# XM125_Breakout.net
KiCad netlist of a schematic drawn in EAGLE
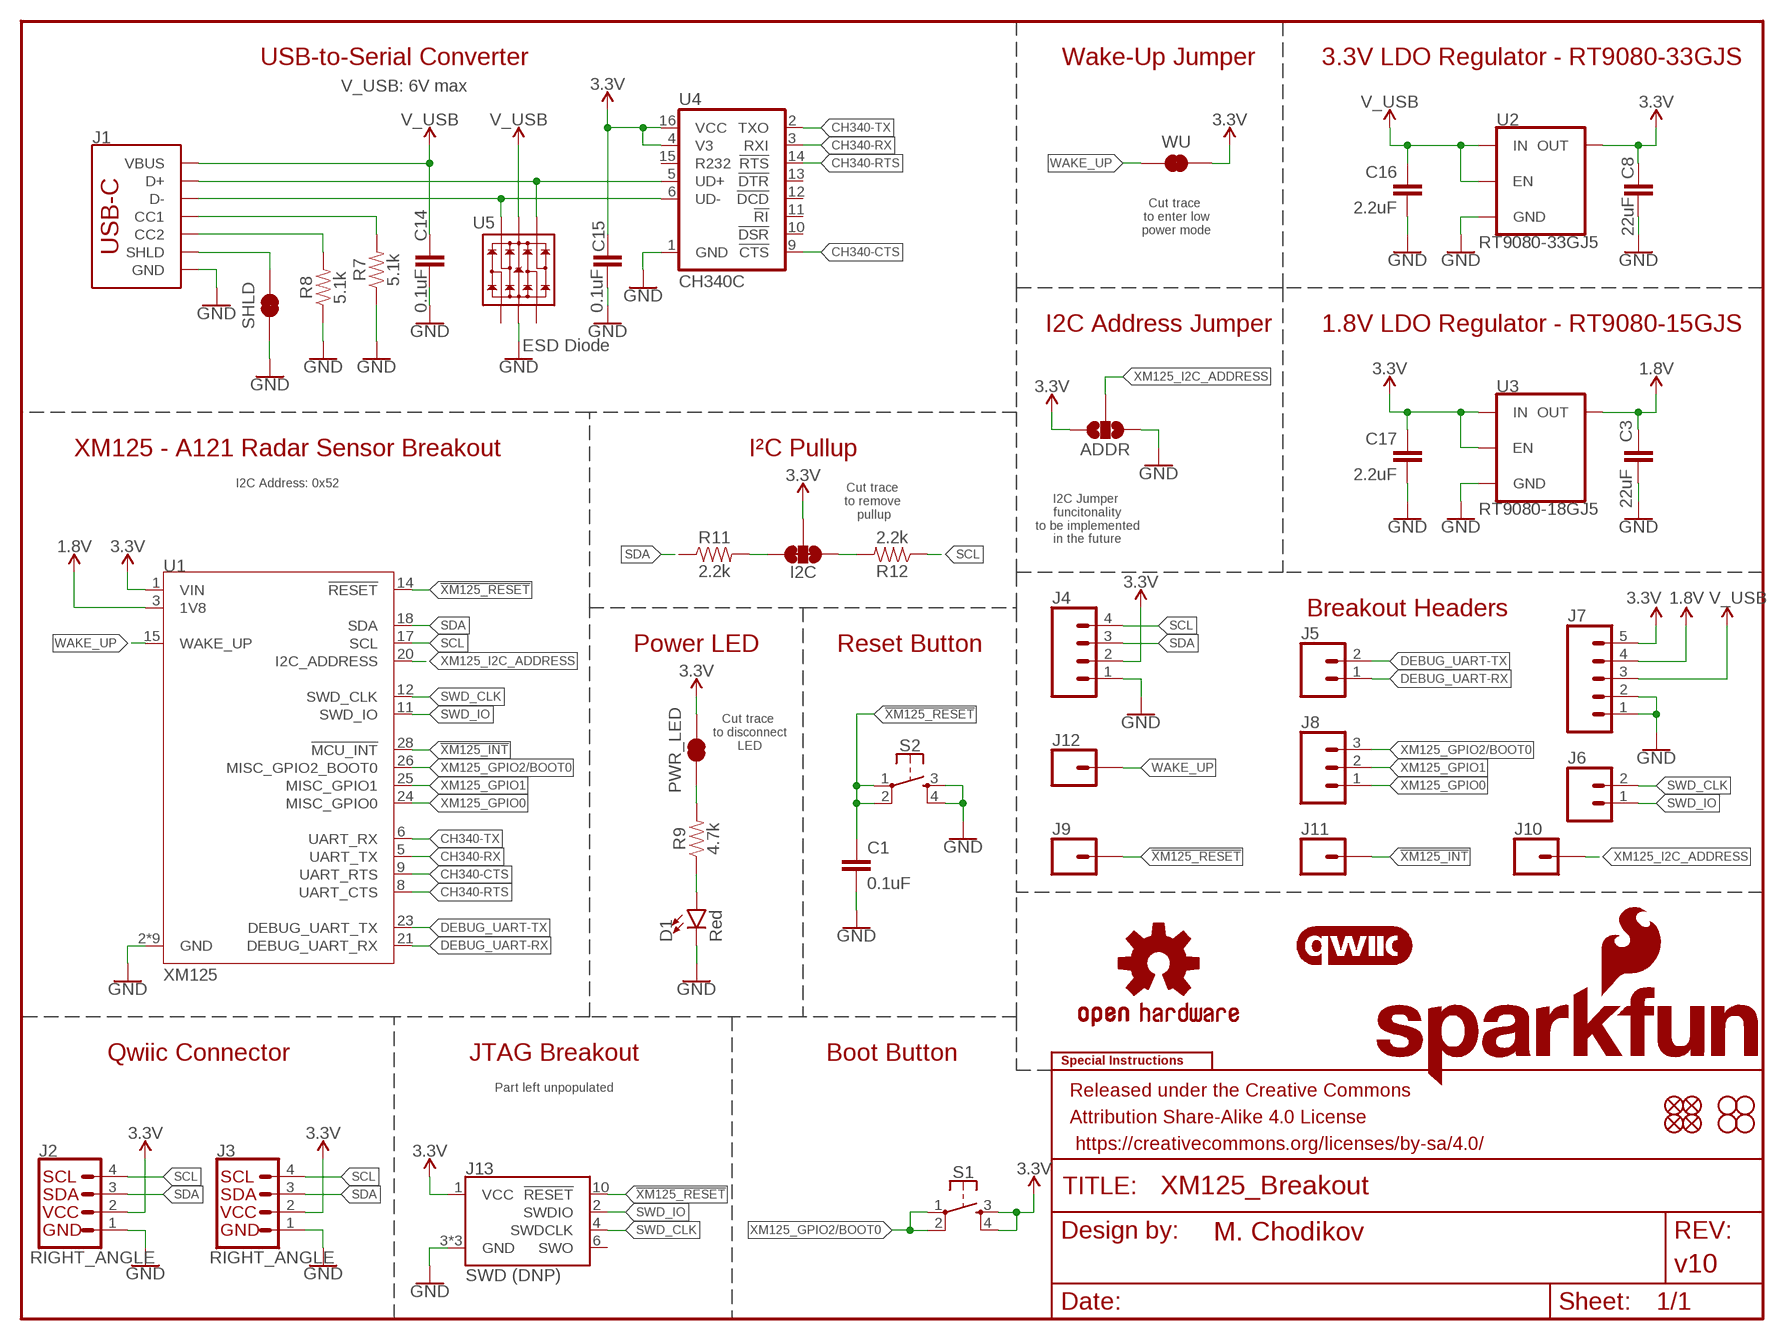
[diagram p0: schematic, sheet 1]

(export (version "E")
  (design (tool "Eeschema 10.0.6"))
  (components
    (comp (ref "ADDR")
      (value "JUMPER-SMT_3_NO_SILK")
      (footprint "eagle-import:SMT-JUMPER_3_NO_SILK")
      (libsource (lib "eagle-import") (part "JUMPER-SMT_3_NO_SILK"))
    )
    (comp (ref "C1")
      (value "0.1uF")
      (footprint "eagle-import:0603")
      (libsource (lib "eagle-import") (part "0.1UF-0603-25V-(+80/-20%)"))
    )
    (comp (ref "C3")
      (value "22uF")
      (footprint "eagle-import:0603")
      (libsource (lib "eagle-import") (part "22UF-0603-6.3V-20%"))
    )
    (comp (ref "C8")
      (value "22uF")
      (footprint "eagle-import:0603")
      (libsource (lib "eagle-import") (part "22UF-0603-6.3V-20%"))
    )
    (comp (ref "C14")
      (value "0.1uF")
      (footprint "eagle-import:0603")
      (libsource (lib "eagle-import") (part "0.1UF-0603-25V-(+80/-20%)"))
    )
    (comp (ref "C15")
      (value "0.1uF")
      (footprint "eagle-import:0603")
      (libsource (lib "eagle-import") (part "0.1UF-0603-25V-(+80/-20%)"))
    )
    (comp (ref "C16")
      (value "2.2uF")
      (footprint "eagle-import:0603")
      (libsource (lib "eagle-import") (part "2.2UF-0603-10V-20%"))
    )
    (comp (ref "C17")
      (value "2.2uF")
      (footprint "eagle-import:0603")
      (libsource (lib "eagle-import") (part "2.2UF-0603-10V-20%"))
    )
    (comp (ref "D1")
      (value "Red")
      (footprint "eagle-import:LED-0603")
      (libsource (lib "eagle-import") (part "LED-RED_0603-KB"))
    )
    (comp (ref "FD1")
      (value "FIDUCIAL1X2")
      (footprint "eagle-import:FIDUCIAL-1X2")
      (libsource (lib "eagle-import") (part "FIDUCIAL1X2"))
    )
    (comp (ref "FD2")
      (value "FIDUCIAL1X2")
      (footprint "eagle-import:FIDUCIAL-1X2")
      (libsource (lib "eagle-import") (part "FIDUCIAL1X2"))
    )
    (comp (ref "FD3")
      (value "FIDUCIAL1X2")
      (footprint "eagle-import:FIDUCIAL-1X2")
      (libsource (lib "eagle-import") (part "FIDUCIAL1X2"))
    )
    (comp (ref "FD4")
      (value "FIDUCIAL1X2")
      (footprint "eagle-import:FIDUCIAL-1X2")
      (libsource (lib "eagle-import") (part "FIDUCIAL1X2"))
    )
    (comp (ref "FRAME2")
      (value "FRAME-LETTER")
      (footprint "eagle-import:CREATIVE_COMMONS")
      (fields (field (name "DESIGNER") "M. Chodikov") (field (name "REV") "v10"))
      (libsource (lib "eagle-import") (part "FRAME-LETTER"))
    )
    (comp (ref "H1")
      (value "STAND-OFF")
      (footprint "eagle-import:STAND-OFF")
      (libsource (lib "eagle-import") (part "STAND-OFF"))
    )
    (comp (ref "H2")
      (value "STAND-OFF")
      (footprint "eagle-import:STAND-OFF")
      (libsource (lib "eagle-import") (part "STAND-OFF"))
    )
    (comp (ref "H3")
      (value "STAND-OFF")
      (footprint "eagle-import:STAND-OFF")
      (libsource (lib "eagle-import") (part "STAND-OFF"))
    )
    (comp (ref "H4")
      (value "STAND-OFF")
      (footprint "eagle-import:STAND-OFF")
      (libsource (lib "eagle-import") (part "STAND-OFF"))
    )
    (comp (ref "I2C")
      (value "JUMPER-SMT_3_2-NC_TRACE_SILK")
      (footprint "eagle-import:SMT-JUMPER_3_2-NC_TRACE_SILK")
      (libsource (lib "eagle-import") (part "JUMPER-SMT_3_2-NC_TRACE_SILK"))
    )
    (comp (ref "J1")
      (value "USB_C_2-LAYER_PADS")
      (footprint "eagle-import:USB-C-16P-2LAYER-PADS")
      (libsource (lib "eagle-import") (part "USB_C_2-LAYER_PADS"))
    )
    (comp (ref "J2")
      (value "RIGHT_ANGLE")
      (footprint "eagle-import:JST04_1MM_RA")
      (libsource (lib "eagle-import") (part "QWIIC_CONNECTORJS-1MM"))
    )
    (comp (ref "J3")
      (value "RIGHT_ANGLE")
      (footprint "eagle-import:JST04_1MM_RA")
      (libsource (lib "eagle-import") (part "QWIIC_CONNECTORJS-1MM"))
    )
    (comp (ref "J4")
      (value "CONN_041X04_NO_SILK")
      (footprint "eagle-import:1X04_NO_SILK")
      (libsource (lib "eagle-import") (part "CONN_041X04_NO_SILK"))
    )
    (comp (ref "J5")
      (value "CONN_021X02_NO_SILK")
      (footprint "eagle-import:1X02_NO_SILK")
      (libsource (lib "eagle-import") (part "CONN_021X02_NO_SILK"))
    )
    (comp (ref "J6")
      (value "CONN_021X02_NO_SILK")
      (footprint "eagle-import:1X02_NO_SILK")
      (libsource (lib "eagle-import") (part "CONN_021X02_NO_SILK"))
    )
    (comp (ref "J7")
      (value "CONN_05NO_SILK")
      (footprint "eagle-import:1X05_NO_SILK")
      (libsource (lib "eagle-import") (part "CONN_05NO_SILK"))
    )
    (comp (ref "J8")
      (value "CONN_031X03_NO_SILK")
      (footprint "eagle-import:1X03_NO_SILK")
      (libsource (lib "eagle-import") (part "CONN_031X03_NO_SILK"))
    )
    (comp (ref "J9")
      (value "CONN_01PTH_NO_SILK_STAND")
      (footprint "eagle-import:1X01_NO_SILK_STAND")
      (libsource (lib "eagle-import") (part "CONN_01PTH_NO_SILK_STAND"))
    )
    (comp (ref "J10")
      (value "CONN_01PTH_NO_SILK_STAND")
      (footprint "eagle-import:1X01_NO_SILK_STAND")
      (libsource (lib "eagle-import") (part "CONN_01PTH_NO_SILK_STAND"))
    )
    (comp (ref "J11")
      (value "CONN_01PTH_NO_SILK_STAND")
      (footprint "eagle-import:1X01_NO_SILK_STAND")
      (libsource (lib "eagle-import") (part "CONN_01PTH_NO_SILK_STAND"))
    )
    (comp (ref "J12")
      (value "CONN_01PTH_NO_SILK_STAND")
      (footprint "eagle-import:1X01_NO_SILK_STAND")
      (libsource (lib "eagle-import") (part "CONN_01PTH_NO_SILK_STAND"))
    )
    (comp (ref "J13")
      (value "SWD (DNP)")
      (footprint "eagle-import:2X5-SMD-UNSHROUDED_DNP_NO_PASTE")
      (libsource (lib "eagle-import") (part "CORTEX_JTAG_DEBUG_MINIMUM_SMD_UNSHROUDED_DNP_NO_PASTE"))
    )
    (comp (ref "LOGO1")
      (value "SPECIAL_INSTRUCTIONS-ORDERING")
      (footprint "eagle-import:ORDERING_INSTRUCTIONS")
      (libsource (lib "eagle-import") (part "SPECIAL_INSTRUCTIONS-ORDERING"))
    )
    (comp (ref "LOGO2")
      (value "QWIIC_LOGO_4MM")
      (footprint "eagle-import:QWIIC_4MM")
      (libsource (lib "eagle-import") (part "QWIIC_LOGO_4MM"))
    )
    (comp (ref "LOGO3")
      (value "SFE_LOGO_NAME_FLAME.1_INCH")
      (footprint "eagle-import:SFE_LOGO_NAME_FLAME_.1")
      (libsource (lib "eagle-import") (part "SFE_LOGO_NAME_FLAME.1_INCH"))
    )
    (comp (ref "LOGO4")
      (value "OSHW-LOGOS")
      (footprint "eagle-import:OSHW-LOGO-S")
      (libsource (lib "eagle-import") (part "OSHW-LOGOS"))
    )
    (comp (ref "LOGO5")
      (value "SFE_LOGO_FLAME.1_INCH")
      (footprint "eagle-import:SFE_LOGO_FLAME_.1")
      (libsource (lib "eagle-import") (part "SFE_LOGO_FLAME.1_INCH"))
    )
    (comp (ref "LOGO6")
      (value "SFE_LOGO_NAME_FLAME.1_INCH")
      (footprint "eagle-import:SFE_LOGO_NAME_FLAME_.1")
      (libsource (lib "eagle-import") (part "SFE_LOGO_NAME_FLAME.1_INCH"))
    )
    (comp (ref "PWR_LED")
      (value "JUMPER-SMT_2_NC_TRACE_SILK")
      (footprint "eagle-import:SMT-JUMPER_2_NC_TRACE_SILK")
      (libsource (lib "eagle-import") (part "JUMPER-SMT_2_NC_TRACE_SILK"))
    )
    (comp (ref "R7")
      (value "5.1k")
      (footprint "eagle-import:0603")
      (libsource (lib "eagle-import") (part "5.1KOHM5.1KOHM-0603-1/10W-1%"))
    )
    (comp (ref "R8")
      (value "5.1k")
      (footprint "eagle-import:0603")
      (libsource (lib "eagle-import") (part "5.1KOHM5.1KOHM-0603-1/10W-1%"))
    )
    (comp (ref "R9")
      (value "4.7k")
      (footprint "eagle-import:0603")
      (libsource (lib "eagle-import") (part "4.7KOHM-0603-1/10W-1%"))
    )
    (comp (ref "R11")
      (value "2.2k")
      (footprint "eagle-import:0603")
      (libsource (lib "eagle-import") (part "2.2KOHM-0603-1/10W-1%"))
    )
    (comp (ref "R12")
      (value "2.2k")
      (footprint "eagle-import:0603")
      (libsource (lib "eagle-import") (part "2.2KOHM-0603-1/10W-1%"))
    )
    (comp (ref "S1")
      (value "MOMENTARY-SWITCH-SPST-2-SMD-5.2MM")
      (footprint "eagle-import:TACTILE_SWITCH_SMD_5.2MM")
      (libsource (lib "eagle-import") (part "MOMENTARY-SWITCH-SPST-2-SMD-5.2MM"))
    )
    (comp (ref "S2")
      (value "MOMENTARY-SWITCH-SPST-2-SMD-5.2MM")
      (footprint "eagle-import:TACTILE_SWITCH_SMD_5.2MM")
      (libsource (lib "eagle-import") (part "MOMENTARY-SWITCH-SPST-2-SMD-5.2MM"))
    )
    (comp (ref "SHLD")
      (value "JUMPER-SMT_2_NC_TRACE_SILK")
      (footprint "eagle-import:SMT-JUMPER_2_NC_TRACE_SILK")
      (libsource (lib "eagle-import") (part "JUMPER-SMT_2_NC_TRACE_SILK"))
    )
    (comp (ref "U1")
      (value "XM125")
      (footprint "eagle-import:XM125_ACC")
      (libsource (lib "eagle-import") (part "XM125"))
    )
    (comp (ref "U2")
      (value "RT9080-33GJ5")
      (footprint "eagle-import:SOT23-5")
      (libsource (lib "eagle-import") (part "V_REG_RT9080"))
    )
    (comp (ref "U3")
      (value "RT9080-18GJ5")
      (footprint "eagle-import:SOT23-5")
      (libsource (lib "eagle-import") (part "RT9080-18GJ5"))
    )
    (comp (ref "U4")
      (value "CH340C")
      (footprint "eagle-import:SO016")
      (libsource (lib "eagle-import") (part "CH340C"))
    )
    (comp (ref "U5")
      (value "ESD Diode")
      (footprint "eagle-import:SOT-23-6")
      (libsource (lib "eagle-import") (part "TVS_DIODE_ARRAY_DT1042-04SO-7"))
    )
    (comp (ref "WU")
      (value "JUMPER-SMT_2_NC_TRACE_SILK")
      (footprint "eagle-import:SMT-JUMPER_2_NC_TRACE_SILK")
      (libsource (lib "eagle-import") (part "JUMPER-SMT_2_NC_TRACE_SILK"))
    )
  )
  (nets
    (net (code "1") (name "/~{XM125_INT}") (class "Default")
      (node (ref "J11") (pin "1") (pinfunction "1_1") (pintype "passive"))
      (node (ref "U1") (pin "28") (pinfunction "~{MCU_INT}_28") (pintype "passive"))
    )
    (net (code "2") (name "/~{XM125_RESET}") (class "Default")
      (node (ref "C1") (pin "2") (pinfunction "2_2") (pintype "passive"))
      (node (ref "J13") (pin "10") (pinfunction "~{RESET}_10") (pintype "bidirectional"))
      (node (ref "J9") (pin "1") (pinfunction "1_1") (pintype "passive"))
      (node (ref "S2") (pin "1") (pinfunction "1_1") (pintype "passive"))
      (node (ref "S2") (pin "2") (pinfunction "2_2") (pintype "passive"))
      (node (ref "U1") (pin "14") (pinfunction "~{RESET}_14") (pintype "passive"))
    )
    (net (code "3") (name "1.8V") (class "Default")
      (node (ref "C3") (pin "1") (pinfunction "1_1") (pintype "passive"))
      (node (ref "J7") (pin "4") (pinfunction "4_4") (pintype "passive"))
      (node (ref "U1") (pin "3") (pinfunction "1V8_3") (pintype "power_in"))
      (node (ref "U3") (pin "5") (pinfunction "OUT_5") (pintype "passive"))
    )
    (net (code "4") (name "3.3V") (class "Default")
      (node (ref "ADDR") (pin "3") (pinfunction "3_3") (pintype "passive"))
      (node (ref "C15") (pin "1") (pinfunction "1_1") (pintype "passive"))
      (node (ref "C17") (pin "1") (pinfunction "1_1") (pintype "passive"))
      (node (ref "C8") (pin "1") (pinfunction "1_1") (pintype "passive"))
      (node (ref "I2C") (pin "2") (pinfunction "2_2") (pintype "passive"))
      (node (ref "J13") (pin "1") (pinfunction "VCC_1") (pintype "bidirectional"))
      (node (ref "J2") (pin "2") (pinfunction "2_2") (pintype "power_in"))
      (node (ref "J3") (pin "2") (pinfunction "2_2") (pintype "power_in"))
      (node (ref "J4") (pin "2") (pinfunction "2_2") (pintype "passive"))
      (node (ref "J7") (pin "5") (pinfunction "5_5") (pintype "passive"))
      (node (ref "PWR_LED") (pin "2") (pinfunction "2_2") (pintype "passive"))
      (node (ref "S1") (pin "3") (pinfunction "3_3") (pintype "passive"))
      (node (ref "S1") (pin "4") (pinfunction "4_4") (pintype "passive"))
      (node (ref "U1") (pin "1") (pinfunction "VIN_1") (pintype "power_in"))
      (node (ref "U2") (pin "5") (pinfunction "OUT_5") (pintype "passive"))
      (node (ref "U3") (pin "1") (pinfunction "IN_1") (pintype "input"))
      (node (ref "U3") (pin "3") (pinfunction "EN_3") (pintype "input"))
      (node (ref "U4") (pin "16") (pinfunction "VCC_16") (pintype "bidirectional"))
      (node (ref "U4") (pin "4") (pinfunction "V3_4") (pintype "bidirectional"))
      (node (ref "WU") (pin "2") (pinfunction "2_2") (pintype "passive"))
    )
    (net (code "5") (name "CH340-CTS") (class "Default")
      (node (ref "U1") (pin "9") (pinfunction "UART_RTS_9") (pintype "passive"))
      (node (ref "U4") (pin "9") (pinfunction "~{CTS}_9") (pintype "bidirectional"))
    )
    (net (code "6") (name "CH340-RTS") (class "Default")
      (node (ref "U1") (pin "8") (pinfunction "UART_CTS_8") (pintype "passive"))
      (node (ref "U4") (pin "14") (pinfunction "~{RTS}_14") (pintype "bidirectional"))
    )
    (net (code "7") (name "CH340-RX") (class "Default")
      (node (ref "U1") (pin "5") (pinfunction "UART_TX_5") (pintype "passive"))
      (node (ref "U4") (pin "3") (pinfunction "RXI_3") (pintype "bidirectional"))
    )
    (net (code "8") (name "CH340-TX") (class "Default")
      (node (ref "U1") (pin "6") (pinfunction "UART_RX_6") (pintype "passive"))
      (node (ref "U4") (pin "2") (pinfunction "TXO_2") (pintype "bidirectional"))
    )
    (net (code "9") (name "DEBUG_UART-RX") (class "Default")
      (node (ref "J5") (pin "1") (pinfunction "1_1") (pintype "passive"))
      (node (ref "U1") (pin "21") (pinfunction "DEBUG_UART_RX_21") (pintype "passive"))
    )
    (net (code "10") (name "DEBUG_UART-TX") (class "Default")
      (node (ref "J5") (pin "2") (pinfunction "2_2") (pintype "passive"))
      (node (ref "U1") (pin "23") (pinfunction "DEBUG_UART_TX_23") (pintype "passive"))
    )
    (net (code "11") (name "GND") (class "Default")
      (node (ref "ADDR") (pin "1") (pinfunction "1_1") (pintype "passive"))
      (node (ref "C1") (pin "1") (pinfunction "1_1") (pintype "passive"))
      (node (ref "C14") (pin "2") (pinfunction "2_2") (pintype "passive"))
      (node (ref "C15") (pin "2") (pinfunction "2_2") (pintype "passive"))
      (node (ref "C16") (pin "2") (pinfunction "2_2") (pintype "passive"))
      (node (ref "C17") (pin "2") (pinfunction "2_2") (pintype "passive"))
      (node (ref "C3") (pin "2") (pinfunction "2_2") (pintype "passive"))
      (node (ref "C8") (pin "2") (pinfunction "2_2") (pintype "passive"))
      (node (ref "D1") (pin "C") (pinfunction "C_C") (pintype "passive"))
      (node (ref "J1") (pin "GND") (pinfunction "GND_GND") (pintype "bidirectional"))
      (node (ref "J1") (pin "GND2") (pinfunction "GND_GND2") (pintype "bidirectional"))
      (node (ref "J13") (pin "3") (pinfunction "GND_3") (pintype "bidirectional"))
      (node (ref "J13") (pin "5") (pinfunction "GND_5") (pintype "bidirectional"))
      (node (ref "J13") (pin "9") (pinfunction "GND_9") (pintype "bidirectional"))
      (node (ref "J2") (pin "1") (pinfunction "1_1") (pintype "power_in"))
      (node (ref "J3") (pin "1") (pinfunction "1_1") (pintype "power_in"))
      (node (ref "J4") (pin "1") (pinfunction "1_1") (pintype "passive"))
      (node (ref "J7") (pin "1") (pinfunction "1_1") (pintype "passive"))
      (node (ref "J7") (pin "2") (pinfunction "2_2") (pintype "passive"))
      (node (ref "R7") (pin "1") (pinfunction "1_1") (pintype "passive"))
      (node (ref "R8") (pin "1") (pinfunction "1_1") (pintype "passive"))
      (node (ref "S2") (pin "3") (pinfunction "3_3") (pintype "passive"))
      (node (ref "S2") (pin "4") (pinfunction "4_4") (pintype "passive"))
      (node (ref "SHLD") (pin "1") (pinfunction "1_1") (pintype "passive"))
      (node (ref "U1") (pin "10") (pinfunction "GND_10") (pintype "passive"))
      (node (ref "U1") (pin "13") (pinfunction "GND_13") (pintype "passive"))
      (node (ref "U1") (pin "16") (pinfunction "GND_16") (pintype "passive"))
      (node (ref "U1") (pin "19") (pinfunction "GND_19") (pintype "passive"))
      (node (ref "U1") (pin "2") (pinfunction "GND_2") (pintype "passive"))
      (node (ref "U1") (pin "22") (pinfunction "GND_22") (pintype "passive"))
      (node (ref "U1") (pin "27") (pinfunction "GND_27") (pintype "passive"))
      (node (ref "U1") (pin "4") (pinfunction "GND_4") (pintype "passive"))
      (node (ref "U1") (pin "7") (pinfunction "GND_7") (pintype "passive"))
      (node (ref "U2") (pin "2") (pinfunction "GND_2") (pintype "input"))
      (node (ref "U3") (pin "2") (pinfunction "GND_2") (pintype "input"))
      (node (ref "U4") (pin "1") (pinfunction "GND_1") (pintype "bidirectional"))
      (node (ref "U5") (pin "2") (pinfunction "VSS_2") (pintype "bidirectional"))
    )
    (net (code "12") (name "Net-(D1-PadA)") (class "Default")
      (node (ref "D1") (pin "A") (pinfunction "A_A") (pintype "passive"))
      (node (ref "R9") (pin "1") (pinfunction "1_1") (pintype "passive"))
    )
    (net (code "13") (name "Net-(I2C-Pad1)") (class "Default")
      (node (ref "I2C") (pin "1") (pinfunction "1_1") (pintype "passive"))
      (node (ref "R12") (pin "2") (pinfunction "2_2") (pintype "passive"))
    )
    (net (code "14") (name "Net-(I2C-Pad3)") (class "Default")
      (node (ref "I2C") (pin "3") (pinfunction "3_3") (pintype "passive"))
      (node (ref "R11") (pin "2") (pinfunction "2_2") (pintype "passive"))
    )
    (net (code "15") (name "Net-(J1-CC1)") (class "Default")
      (node (ref "J1") (pin "A5") (pinfunction "CC1_A5") (pintype "bidirectional"))
      (node (ref "R7") (pin "2") (pinfunction "2_2") (pintype "passive"))
    )
    (net (code "16") (name "Net-(J1-CC2)") (class "Default")
      (node (ref "J1") (pin "B5") (pinfunction "CC2_B5") (pintype "bidirectional"))
      (node (ref "R8") (pin "2") (pinfunction "2_2") (pintype "passive"))
    )
    (net (code "17") (name "Net-(J1-SHLD-PadSHLD1)") (class "Default")
      (node (ref "J1") (pin "SHLD1") (pinfunction "SHLD_SHLD1") (pintype "bidirectional"))
      (node (ref "J1") (pin "SHLD2") (pinfunction "SHLD_SHLD2") (pintype "bidirectional"))
      (node (ref "J1") (pin "SHLD3") (pinfunction "SHLD_SHLD3") (pintype "bidirectional"))
      (node (ref "J1") (pin "SHLD4") (pinfunction "SHLD_SHLD4") (pintype "bidirectional"))
      (node (ref "SHLD") (pin "2") (pinfunction "2_2") (pintype "passive"))
    )
    (net (code "18") (name "Net-(PWR_LED-Pad1)") (class "Default")
      (node (ref "PWR_LED") (pin "1") (pinfunction "1_1") (pintype "passive"))
      (node (ref "R9") (pin "2") (pinfunction "2_2") (pintype "passive"))
    )
    (net (code "19") (name "Net-(U4-UD+)") (class "Default")
      (node (ref "J1") (pin "A6") (pinfunction "D+_A6") (pintype "bidirectional"))
      (node (ref "J1") (pin "B6") (pinfunction "D+_B6") (pintype "bidirectional"))
      (node (ref "U4") (pin "5") (pinfunction "UD+_5") (pintype "bidirectional"))
      (node (ref "U5") (pin "4") (pinfunction "IO3_4") (pintype "bidirectional"))
    )
    (net (code "20") (name "Net-(U4-UD-)") (class "Default")
      (node (ref "J1") (pin "A7") (pinfunction "D-_A7") (pintype "bidirectional"))
      (node (ref "J1") (pin "B7") (pinfunction "D-_B7") (pintype "bidirectional"))
      (node (ref "U4") (pin "6") (pinfunction "UD-_6") (pintype "bidirectional"))
      (node (ref "U5") (pin "6") (pinfunction "IO4_6") (pintype "bidirectional"))
    )
    (net (code "21") (name "SCL") (class "Default")
      (node (ref "J2") (pin "4") (pinfunction "4_4") (pintype "passive"))
      (node (ref "J3") (pin "4") (pinfunction "4_4") (pintype "passive"))
      (node (ref "J4") (pin "4") (pinfunction "4_4") (pintype "passive"))
      (node (ref "R12") (pin "1") (pinfunction "1_1") (pintype "passive"))
      (node (ref "U1") (pin "17") (pinfunction "SCL_17") (pintype "passive"))
    )
    (net (code "22") (name "SDA") (class "Default")
      (node (ref "J2") (pin "3") (pinfunction "3_3") (pintype "passive"))
      (node (ref "J3") (pin "3") (pinfunction "3_3") (pintype "passive"))
      (node (ref "J4") (pin "3") (pinfunction "3_3") (pintype "passive"))
      (node (ref "R11") (pin "1") (pinfunction "1_1") (pintype "passive"))
      (node (ref "U1") (pin "18") (pinfunction "SDA_18") (pintype "passive"))
    )
    (net (code "23") (name "SWD_CLK") (class "Default")
      (node (ref "J13") (pin "4") (pinfunction "SWDCLK_4") (pintype "bidirectional"))
      (node (ref "J6") (pin "2") (pinfunction "2_2") (pintype "passive"))
      (node (ref "U1") (pin "12") (pinfunction "SWD_CLK_12") (pintype "passive"))
    )
    (net (code "24") (name "SWD_IO") (class "Default")
      (node (ref "J13") (pin "2") (pinfunction "SWDIO_2") (pintype "bidirectional"))
      (node (ref "J6") (pin "1") (pinfunction "1_1") (pintype "passive"))
      (node (ref "U1") (pin "11") (pinfunction "SWD_IO_11") (pintype "passive"))
    )
    (net (code "25") (name "V_USB") (class "Default")
      (node (ref "C14") (pin "1") (pinfunction "1_1") (pintype "passive"))
      (node (ref "C16") (pin "1") (pinfunction "1_1") (pintype "passive"))
      (node (ref "J1") (pin "VBUS1") (pinfunction "VBUS_VBUS1") (pintype "bidirectional"))
      (node (ref "J1") (pin "VBUS2") (pinfunction "VBUS_VBUS2") (pintype "bidirectional"))
      (node (ref "J7") (pin "3") (pinfunction "3_3") (pintype "passive"))
      (node (ref "U2") (pin "1") (pinfunction "IN_1") (pintype "input"))
      (node (ref "U2") (pin "3") (pinfunction "EN_3") (pintype "input"))
      (node (ref "U5") (pin "5") (pinfunction "VCC_5") (pintype "bidirectional"))
    )
    (net (code "26") (name "WAKE_UP") (class "Default")
      (node (ref "J12") (pin "1") (pinfunction "1_1") (pintype "passive"))
      (node (ref "U1") (pin "15") (pinfunction "WAKE_UP_15") (pintype "passive"))
      (node (ref "WU") (pin "1") (pinfunction "1_1") (pintype "passive"))
    )
    (net (code "27") (name "XM125_GPIO0") (class "Default")
      (node (ref "J8") (pin "1") (pinfunction "1_1") (pintype "passive"))
      (node (ref "U1") (pin "24") (pinfunction "MISC_GPIO0_24") (pintype "bidirectional"))
    )
    (net (code "28") (name "XM125_GPIO1") (class "Default")
      (node (ref "J8") (pin "2") (pinfunction "2_2") (pintype "passive"))
      (node (ref "U1") (pin "25") (pinfunction "MISC_GPIO1_25") (pintype "bidirectional"))
    )
    (net (code "29") (name "XM125_GPIO2{slash}BOOT0") (class "Default")
      (node (ref "J8") (pin "3") (pinfunction "3_3") (pintype "passive"))
      (node (ref "S1") (pin "1") (pinfunction "1_1") (pintype "passive"))
      (node (ref "S1") (pin "2") (pinfunction "2_2") (pintype "passive"))
      (node (ref "U1") (pin "26") (pinfunction "MISC_GPIO2_BOOT0_26") (pintype "bidirectional"))
    )
    (net (code "30") (name "XM125_I2C_ADDRESS") (class "Default")
      (node (ref "ADDR") (pin "2") (pinfunction "2_2") (pintype "passive"))
      (node (ref "J10") (pin "1") (pinfunction "1_1") (pintype "passive"))
      (node (ref "U1") (pin "20") (pinfunction "I2C_ADDRESS_20") (pintype "passive"))
    )
    (net (code "31") (name "unconnected-(J13-SWO-Pad6)") (class "Default")
      (node (ref "J13") (pin "6") (pinfunction "SWO_6") (pintype "bidirectional"))
    )
    (net (code "32") (name "unconnected-(U4-R232-Pad15)") (class "Default")
      (node (ref "U4") (pin "15") (pinfunction "R232_15") (pintype "bidirectional"))
    )
    (net (code "33") (name "unconnected-(U4-~{DCD}-Pad12)") (class "Default")
      (node (ref "U4") (pin "12") (pinfunction "~{DCD}_12") (pintype "bidirectional"))
    )
    (net (code "34") (name "unconnected-(U4-~{DSR}-Pad10)") (class "Default")
      (node (ref "U4") (pin "10") (pinfunction "~{DSR}_10") (pintype "bidirectional"))
    )
    (net (code "35") (name "unconnected-(U4-~{DTR}-Pad13)") (class "Default")
      (node (ref "U4") (pin "13") (pinfunction "~{DTR}_13") (pintype "bidirectional"))
    )
    (net (code "36") (name "unconnected-(U4-~{RI}-Pad11)") (class "Default")
      (node (ref "U4") (pin "11") (pinfunction "~{RI}_11") (pintype "bidirectional"))
    )
    (net (code "37") (name "unconnected-(U5-IO1-Pad1)") (class "Default")
      (node (ref "U5") (pin "1") (pinfunction "IO1_1") (pintype "bidirectional"))
    )
    (net (code "38") (name "unconnected-(U5-IO2-Pad3)") (class "Default")
      (node (ref "U5") (pin "3") (pinfunction "IO2_3") (pintype "bidirectional"))
    )
  )
)
